# bilancia_smart_pezzi_uc.net
KiCad netlist of a schematic drawn in EAGLE
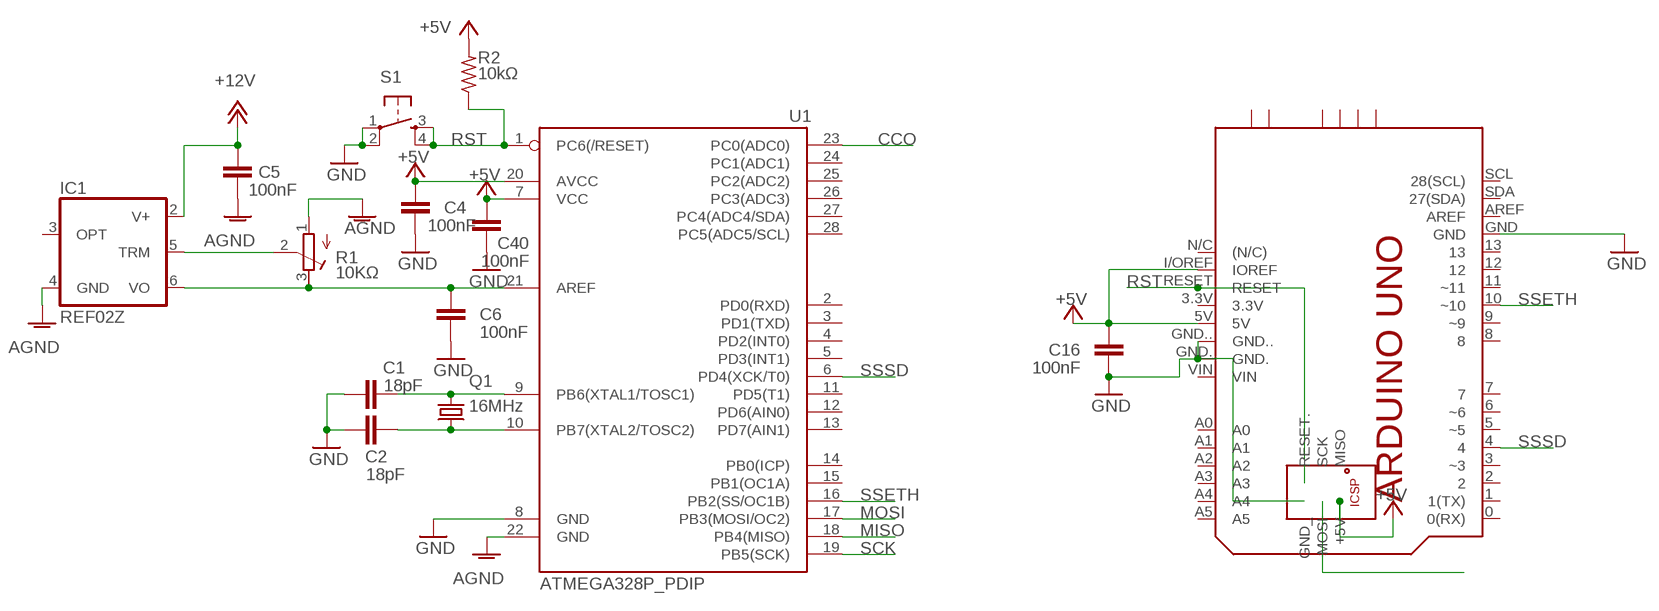
[diagram p0: schematic, sheet 1]

(export (version "E")
  (design (tool "Eeschema 10.0.6"))
  (components
    (comp (ref "C1")
      (value "18pF")
      (footprint "eagle-import:C2.5-2")
      (libsource (lib "eagle-import") (part "C2.5/2"))
    )
    (comp (ref "C2")
      (value "18pF")
      (footprint "eagle-import:C2.5-2")
      (libsource (lib "eagle-import") (part "C2.5/2"))
    )
    (comp (ref "C4")
      (value "100nF")
      (footprint "eagle-import:C2.5-2")
      (libsource (lib "eagle-import") (part "C2.5/2"))
    )
    (comp (ref "C5")
      (value "100nF")
      (footprint "eagle-import:C2.5-2")
      (libsource (lib "eagle-import") (part "C2.5/2"))
    )
    (comp (ref "C6")
      (value "100nF")
      (footprint "eagle-import:C2.5-2")
      (libsource (lib "eagle-import") (part "C2.5/2"))
    )
    (comp (ref "C16")
      (value "100nF")
      (footprint "eagle-import:C2.5-2")
      (libsource (lib "eagle-import") (part "C2.5/2"))
    )
    (comp (ref "C40")
      (value "100nF")
      (footprint "eagle-import:C2.5-2")
      (libsource (lib "eagle-import") (part "C2.5/2"))
    )
    (comp (ref "IC1")
      (value "REF02Z")
      (footprint "eagle-import:DIL08")
      (libsource (lib "eagle-import") (part "REF02Z"))
    )
    (comp (ref "PCB1")
      (value "ARDUINO_UNO")
      (footprint "eagle-import:ARDUINO_UNO")
      (libsource (lib "eagle-import") (part "ARDUINO_UNO"))
    )
    (comp (ref "Q1")
      (value "16MHz")
      (footprint "eagle-import:HC49_S")
      (libsource (lib "eagle-import") (part "CRYSTALHC49S"))
    )
    (comp (ref "R1")
      (value "10KΩ")
      (footprint "eagle-import:RTRIM64W")
      (libsource (lib "eagle-import") (part "R-TRIMM64W"))
    )
    (comp (ref "R2")
      (value "10kΩ")
      (footprint "eagle-import:0207_10")
      (libsource (lib "eagle-import") (part "R-US_0207/10"))
    )
    (comp (ref "S1")
      (value "TAC_SWITCHPTH")
      (footprint "eagle-import:TACTILE-PTH")
      (libsource (lib "eagle-import") (part "TAC_SWITCHPTH"))
    )
    (comp (ref "U1")
      (value "ATMEGA328P_PDIP")
      (footprint "eagle-import:DIL28-3")
      (libsource (lib "eagle-import") (part "ATMEGA328P_PDIP"))
    )
  )
  (nets
    (net (code "1") (name "+5V") (class "Default")
      (node (ref "C16") (pin "2") (pinfunction "2_2") (pintype "passive"))
      (node (ref "C4") (pin "2") (pinfunction "2_2") (pintype "passive"))
      (node (ref "C40") (pin "2") (pinfunction "2_2") (pintype "passive"))
      (node (ref "PCB1") (pin "+5V") (pinfunction "+5V_+5V") (pintype "bidirectional"))
      (node (ref "PCB1") (pin "5V") (pinfunction "5V_5V") (pintype "bidirectional"))
      (node (ref "PCB1") (pin "I/OREF") (pinfunction "IOREF_I/OREF") (pintype "bidirectional"))
      (node (ref "R2") (pin "2") (pinfunction "2_2") (pintype "passive"))
      (node (ref "U1") (pin "20") (pinfunction "AVCC_20") (pintype "bidirectional"))
      (node (ref "U1") (pin "7") (pinfunction "VCC_7") (pintype "bidirectional"))
    )
    (net (code "2") (name "+12V") (class "Default")
      (node (ref "C5") (pin "1") (pinfunction "1_1") (pintype "passive"))
      (node (ref "IC1") (pin "2") (pinfunction "V+_2") (pintype "power_in"))
    )
    (net (code "3") (name "/CCO") (class "Default")
      (node (ref "U1") (pin "23") (pinfunction "PC0(ADC0)_23") (pintype "bidirectional"))
    )
    (net (code "4") (name "/MISO") (class "Default")
      (node (ref "U1") (pin "18") (pinfunction "PB4(MISO)_18") (pintype "bidirectional"))
    )
    (net (code "5") (name "/MOSI") (class "Default")
      (node (ref "PCB1") (pin "MOSI") (pinfunction "MOSI_MOSI") (pintype "bidirectional"))
      (node (ref "U1") (pin "17") (pinfunction "PB3(MOSI/OC2)_17") (pintype "bidirectional"))
    )
    (net (code "6") (name "/RST") (class "Default")
      (node (ref "PCB1") (pin "RESET") (pinfunction "RESET_RESET") (pintype "bidirectional"))
      (node (ref "PCB1") (pin "RESET.") (pinfunction "RESET._RESET.") (pintype "bidirectional"))
      (node (ref "R2") (pin "1") (pinfunction "1_1") (pintype "passive"))
      (node (ref "S1") (pin "3") (pinfunction "3_3") (pintype "passive"))
      (node (ref "S1") (pin "4") (pinfunction "4_4") (pintype "passive"))
      (node (ref "U1") (pin "1") (pinfunction "PC6(/RESET)_1") (pintype "bidirectional"))
    )
    (net (code "7") (name "/SCK") (class "Default")
      (node (ref "U1") (pin "19") (pinfunction "PB5(SCK)_19") (pintype "bidirectional"))
    )
    (net (code "8") (name "/SSETH") (class "Default")
      (node (ref "PCB1") (pin "10") (pinfunction "~{10}_10") (pintype "bidirectional"))
      (node (ref "U1") (pin "16") (pinfunction "PB2(SS/OC1B)_16") (pintype "bidirectional"))
    )
    (net (code "9") (name "/SSSD") (class "Default")
      (node (ref "PCB1") (pin "4") (pinfunction "4_4") (pintype "bidirectional"))
      (node (ref "U1") (pin "6") (pinfunction "PD4(XCK/T0)_6") (pintype "bidirectional"))
    )
    (net (code "10") (name "AGND") (class "Default")
      (node (ref "C5") (pin "2") (pinfunction "2_2") (pintype "passive"))
      (node (ref "IC1") (pin "4") (pinfunction "GND_4") (pintype "power_in"))
      (node (ref "R1") (pin "1") (pinfunction "E_1") (pintype "passive"))
      (node (ref "U1") (pin "22") (pinfunction "GND_22") (pintype "bidirectional"))
    )
    (net (code "11") (name "GND") (class "Default")
      (node (ref "C1") (pin "1") (pinfunction "1_1") (pintype "passive"))
      (node (ref "C16") (pin "1") (pinfunction "1_1") (pintype "passive"))
      (node (ref "C2") (pin "1") (pinfunction "1_1") (pintype "passive"))
      (node (ref "C4") (pin "1") (pinfunction "1_1") (pintype "passive"))
      (node (ref "C40") (pin "1") (pinfunction "1_1") (pintype "passive"))
      (node (ref "C6") (pin "1") (pinfunction "1_1") (pintype "passive"))
      (node (ref "PCB1") (pin "GND") (pinfunction "GND_GND") (pintype "bidirectional"))
      (node (ref "PCB1") (pin "GND.") (pinfunction "GND._GND.") (pintype "bidirectional"))
      (node (ref "PCB1") (pin "GND..") (pinfunction "GND.._GND..") (pintype "bidirectional"))
      (node (ref "PCB1") (pin "GND_") (pinfunction "GND__GND_") (pintype "bidirectional"))
      (node (ref "S1") (pin "1") (pinfunction "1_1") (pintype "passive"))
      (node (ref "S1") (pin "2") (pinfunction "2_2") (pintype "passive"))
      (node (ref "U1") (pin "8") (pinfunction "GND_8") (pintype "bidirectional"))
    )
    (net (code "12") (name "Net-(IC1-TRM)") (class "Default")
      (node (ref "IC1") (pin "5") (pinfunction "TRM_5") (pintype "input"))
      (node (ref "R1") (pin "2") (pinfunction "S_2") (pintype "passive"))
    )
    (net (code "13") (name "Net-(IC1-VO)") (class "Default")
      (node (ref "C6") (pin "2") (pinfunction "2_2") (pintype "passive"))
      (node (ref "IC1") (pin "6") (pinfunction "VO_6") (pintype "output"))
      (node (ref "R1") (pin "3") (pinfunction "A_3") (pintype "passive"))
      (node (ref "U1") (pin "21") (pinfunction "AREF_21") (pintype "bidirectional"))
    )
    (net (code "14") (name "Net-(U1-PB6(XTAL1{slash}TOSC1))") (class "Default")
      (node (ref "C1") (pin "2") (pinfunction "2_2") (pintype "passive"))
      (node (ref "Q1") (pin "1") (pinfunction "1_1") (pintype "passive"))
      (node (ref "U1") (pin "9") (pinfunction "PB6(XTAL1/TOSC1)_9") (pintype "bidirectional"))
    )
    (net (code "15") (name "Net-(U1-PB7(XTAL2{slash}TOSC2))") (class "Default")
      (node (ref "C2") (pin "2") (pinfunction "2_2") (pintype "passive"))
      (node (ref "Q1") (pin "2") (pinfunction "2_2") (pintype "passive"))
      (node (ref "U1") (pin "10") (pinfunction "PB7(XTAL2/TOSC2)_10") (pintype "bidirectional"))
    )
    (net (code "16") (name "unconnected-(IC1-OPT-Pad3)") (class "Default")
      (node (ref "IC1") (pin "3") (pinfunction "OPT_3") (pintype "output"))
    )
    (net (code "17") (name "unconnected-(PCB1-(N{slash}C)-PadN{slash}C)") (class "Default")
      (node (ref "PCB1") (pin "N/C") (pinfunction "(N/C)_N/C") (pintype "bidirectional"))
    )
    (net (code "18") (name "unconnected-(PCB1-0(RX)-Pad0)") (class "Default")
      (node (ref "PCB1") (pin "0") (pinfunction "0(RX)_0") (pintype "bidirectional"))
    )
    (net (code "19") (name "unconnected-(PCB1-1(TX)-Pad1)") (class "Default")
      (node (ref "PCB1") (pin "1") (pinfunction "1(TX)_1") (pintype "bidirectional"))
    )
    (net (code "20") (name "unconnected-(PCB1-27(SDA)-PadSDA)") (class "Default")
      (node (ref "PCB1") (pin "SDA") (pinfunction "27(SDA)_SDA") (pintype "bidirectional"))
    )
    (net (code "21") (name "unconnected-(PCB1-28(SCL)-PadSCL)") (class "Default")
      (node (ref "PCB1") (pin "SCL") (pinfunction "28(SCL)_SCL") (pintype "bidirectional"))
    )
    (net (code "22") (name "unconnected-(PCB1-Pad2)") (class "Default")
      (node (ref "PCB1") (pin "2") (pinfunction "2_2") (pintype "bidirectional"))
    )
    (net (code "23") (name "unconnected-(PCB1-Pad3.3V)") (class "Default")
      (node (ref "PCB1") (pin "3.3V") (pinfunction "3.3V_3.3V") (pintype "bidirectional"))
    )
    (net (code "24") (name "unconnected-(PCB1-Pad7)") (class "Default")
      (node (ref "PCB1") (pin "7") (pinfunction "7_7") (pintype "bidirectional"))
    )
    (net (code "25") (name "unconnected-(PCB1-Pad8)") (class "Default")
      (node (ref "PCB1") (pin "8") (pinfunction "8_8") (pintype "bidirectional"))
    )
    (net (code "26") (name "unconnected-(PCB1-Pad12)") (class "Default")
      (node (ref "PCB1") (pin "12") (pinfunction "12_12") (pintype "bidirectional"))
    )
    (net (code "27") (name "unconnected-(PCB1-Pad13)") (class "Default")
      (node (ref "PCB1") (pin "13") (pinfunction "13_13") (pintype "bidirectional"))
    )
    (net (code "28") (name "unconnected-(PCB1-Pad<PWR>+V)") (class "Default")
      (node (ref "PCB1") (pin "<PWR>+V") (pinfunction "<PWR>+V_<PWR>+V") (pintype "bidirectional"))
    )
    (net (code "29") (name "unconnected-(PCB1-Pad<PWR>-V)") (class "Default")
      (node (ref "PCB1") (pin "<PWR>-V") (pinfunction "<PWR>-V_<PWR>-V") (pintype "bidirectional"))
    )
    (net (code "30") (name "unconnected-(PCB1-Pad<USB>+V)") (class "Default")
      (node (ref "PCB1") (pin "<USB>+V") (pinfunction "<USB>+V_<USB>+V") (pintype "bidirectional"))
    )
    (net (code "31") (name "unconnected-(PCB1-Pad<USB>D+)") (class "Default")
      (node (ref "PCB1") (pin "<USB>D+") (pinfunction "<USB>D+_<USB>D+") (pintype "bidirectional"))
    )
    (net (code "32") (name "unconnected-(PCB1-Pad<USB>D-)") (class "Default")
      (node (ref "PCB1") (pin "<USB>D-") (pinfunction "<USB>D-_<USB>D-") (pintype "bidirectional"))
    )
    (net (code "33") (name "unconnected-(PCB1-Pad<USB>GND)") (class "Default")
      (node (ref "PCB1") (pin "<USB>GND") (pinfunction "<USB>GND_<USB>GND") (pintype "bidirectional"))
    )
    (net (code "34") (name "unconnected-(PCB1-PadA0)") (class "Default")
      (node (ref "PCB1") (pin "A0") (pinfunction "A0_A0") (pintype "bidirectional"))
    )
    (net (code "35") (name "unconnected-(PCB1-PadA1)") (class "Default")
      (node (ref "PCB1") (pin "A1") (pinfunction "A1_A1") (pintype "bidirectional"))
    )
    (net (code "36") (name "unconnected-(PCB1-PadA2)") (class "Default")
      (node (ref "PCB1") (pin "A2") (pinfunction "A2_A2") (pintype "bidirectional"))
    )
    (net (code "37") (name "unconnected-(PCB1-PadA3)") (class "Default")
      (node (ref "PCB1") (pin "A3") (pinfunction "A3_A3") (pintype "bidirectional"))
    )
    (net (code "38") (name "unconnected-(PCB1-PadA4)") (class "Default")
      (node (ref "PCB1") (pin "A4") (pinfunction "A4_A4") (pintype "bidirectional"))
    )
    (net (code "39") (name "unconnected-(PCB1-PadA5)") (class "Default")
      (node (ref "PCB1") (pin "A5") (pinfunction "A5_A5") (pintype "bidirectional"))
    )
    (net (code "40") (name "unconnected-(PCB1-PadAREF)") (class "Default")
      (node (ref "PCB1") (pin "AREF") (pinfunction "AREF_AREF") (pintype "bidirectional"))
    )
    (net (code "41") (name "unconnected-(PCB1-PadMISO)") (class "Default")
      (node (ref "PCB1") (pin "MISO") (pinfunction "MISO_MISO") (pintype "bidirectional"))
    )
    (net (code "42") (name "unconnected-(PCB1-PadSCK)") (class "Default")
      (node (ref "PCB1") (pin "SCK") (pinfunction "SCK_SCK") (pintype "bidirectional"))
    )
    (net (code "43") (name "unconnected-(PCB1-PadVIN)") (class "Default")
      (node (ref "PCB1") (pin "VIN") (pinfunction "VIN_VIN") (pintype "bidirectional"))
    )
    (net (code "44") (name "unconnected-(PCB1-~{3}-Pad3)") (class "Default")
      (node (ref "PCB1") (pin "3") (pinfunction "~{3}_3") (pintype "bidirectional"))
    )
    (net (code "45") (name "unconnected-(PCB1-~{5}-Pad5)") (class "Default")
      (node (ref "PCB1") (pin "5") (pinfunction "~{5}_5") (pintype "bidirectional"))
    )
    (net (code "46") (name "unconnected-(PCB1-~{6}-Pad6)") (class "Default")
      (node (ref "PCB1") (pin "6") (pinfunction "~{6}_6") (pintype "bidirectional"))
    )
    (net (code "47") (name "unconnected-(PCB1-~{9}-Pad9)") (class "Default")
      (node (ref "PCB1") (pin "9") (pinfunction "~{9}_9") (pintype "bidirectional"))
    )
    (net (code "48") (name "unconnected-(PCB1-~{11}-Pad11)") (class "Default")
      (node (ref "PCB1") (pin "11") (pinfunction "~{11}_11") (pintype "bidirectional"))
    )
    (net (code "49") (name "unconnected-(U1-PB0(ICP)-Pad14)") (class "Default")
      (node (ref "U1") (pin "14") (pinfunction "PB0(ICP)_14") (pintype "bidirectional"))
    )
    (net (code "50") (name "unconnected-(U1-PB1(OC1A)-Pad15)") (class "Default")
      (node (ref "U1") (pin "15") (pinfunction "PB1(OC1A)_15") (pintype "bidirectional"))
    )
    (net (code "51") (name "unconnected-(U1-PC1(ADC1)-Pad24)") (class "Default")
      (node (ref "U1") (pin "24") (pinfunction "PC1(ADC1)_24") (pintype "bidirectional"))
    )
    (net (code "52") (name "unconnected-(U1-PC2(ADC2)-Pad25)") (class "Default")
      (node (ref "U1") (pin "25") (pinfunction "PC2(ADC2)_25") (pintype "bidirectional"))
    )
    (net (code "53") (name "unconnected-(U1-PC3(ADC3)-Pad26)") (class "Default")
      (node (ref "U1") (pin "26") (pinfunction "PC3(ADC3)_26") (pintype "bidirectional"))
    )
    (net (code "54") (name "unconnected-(U1-PC4(ADC4{slash}SDA)-Pad27)") (class "Default")
      (node (ref "U1") (pin "27") (pinfunction "PC4(ADC4/SDA)_27") (pintype "bidirectional"))
    )
    (net (code "55") (name "unconnected-(U1-PC5(ADC5{slash}SCL)-Pad28)") (class "Default")
      (node (ref "U1") (pin "28") (pinfunction "PC5(ADC5/SCL)_28") (pintype "bidirectional"))
    )
    (net (code "56") (name "unconnected-(U1-PD0(RXD)-Pad2)") (class "Default")
      (node (ref "U1") (pin "2") (pinfunction "PD0(RXD)_2") (pintype "bidirectional"))
    )
    (net (code "57") (name "unconnected-(U1-PD1(TXD)-Pad3)") (class "Default")
      (node (ref "U1") (pin "3") (pinfunction "PD1(TXD)_3") (pintype "bidirectional"))
    )
    (net (code "58") (name "unconnected-(U1-PD2(INT0)-Pad4)") (class "Default")
      (node (ref "U1") (pin "4") (pinfunction "PD2(INT0)_4") (pintype "bidirectional"))
    )
    (net (code "59") (name "unconnected-(U1-PD3(INT1)-Pad5)") (class "Default")
      (node (ref "U1") (pin "5") (pinfunction "PD3(INT1)_5") (pintype "bidirectional"))
    )
    (net (code "60") (name "unconnected-(U1-PD5(T1)-Pad11)") (class "Default")
      (node (ref "U1") (pin "11") (pinfunction "PD5(T1)_11") (pintype "bidirectional"))
    )
    (net (code "61") (name "unconnected-(U1-PD6(AIN0)-Pad12)") (class "Default")
      (node (ref "U1") (pin "12") (pinfunction "PD6(AIN0)_12") (pintype "bidirectional"))
    )
    (net (code "62") (name "unconnected-(U1-PD7(AIN1)-Pad13)") (class "Default")
      (node (ref "U1") (pin "13") (pinfunction "PD7(AIN1)_13") (pintype "bidirectional"))
    )
  )
)
